# TickTagREV4.net
KiCad netlist of a schematic drawn in EAGLE
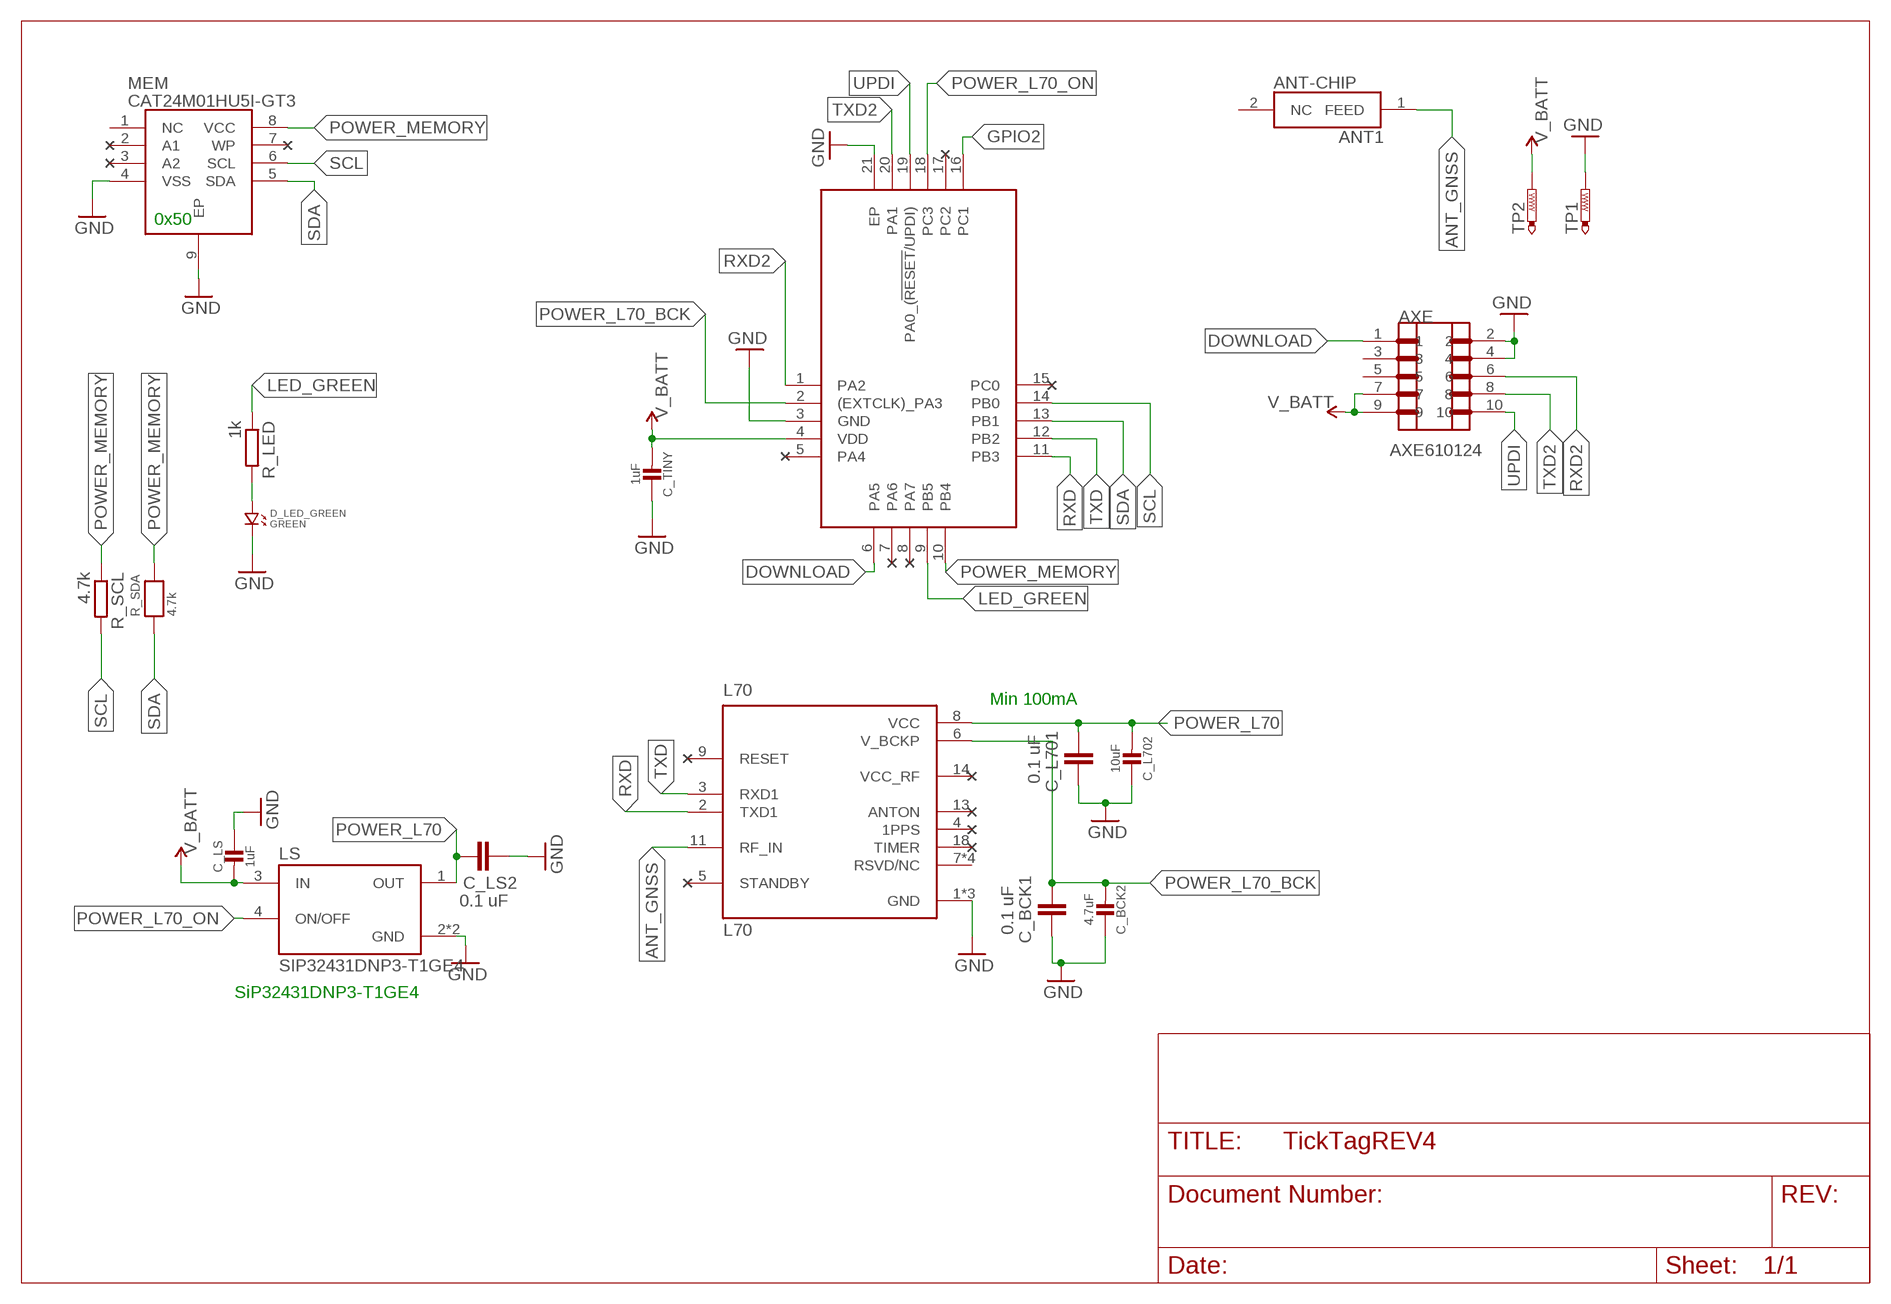
[diagram p0: schematic, sheet 1]

(export (version "E")
  (design (tool "Eeschema 10.0.6"))
  (components
    (comp (ref "ANT-CHIP")
      (value "ANT1")
      (footprint "eagle-import:SAMACSYS_PARTS_1575AT43A0040E")
      (fields
        (field (name "MANUFACTURER_PART_NUMBER") "1575AT43A0040E")
        (field (name "MOUSER_PART_NUMBER") "609-1575AT43A0040E")
      )
      (libsource (lib "eagle-import") (part "SAMACSYS_PARTS_1575AT43A0040E"))
    )
    (comp (ref "ATTINY")
      (value "ATTINY1616-MFR")
      (footprint "eagle-import:QFN40P300X300X90-21N")
      (fields
        (field (name "MANUFACTURER_PART_NUMBER") "ATTINY1606-MFR")
        (field (name "MOUSER_PART_NUMBER") "556-ATTINY1606-MFR")
      )
      (libsource (lib "eagle-import") (part "ATTINY1616-MFR"))
    )
    (comp (ref "AXE")
      (value "AXE610124")
      (footprint "eagle-import:AXE610124")
      (libsource (lib "eagle-import") (part "AXE610124"))
    )
    (comp (ref "C_BCK1")
      (value "0.1 uF")
      (footprint "eagle-import:C0201")
      (libsource (lib "eagle-import") (part "C-EUC0201"))
    )
    (comp (ref "C_BCK2")
      (value "4.7uF")
      (footprint "eagle-import:MICROBUILDER__0402MP")
      (libsource (lib "eagle-import") (part "MICROBUILDER_CAP_CERAMIC_0402MP"))
    )
    (comp (ref "C_L701")
      (value "0.1 uF")
      (footprint "eagle-import:C0201")
      (libsource (lib "eagle-import") (part "C-EUC0201"))
    )
    (comp (ref "C_L702")
      (value "10uF")
      (footprint "eagle-import:MICROBUILDER__0402MP")
      (libsource (lib "eagle-import") (part "MICROBUILDER_CAP_CERAMIC_0402MP"))
    )
    (comp (ref "C_LS")
      (value "1uF")
      (footprint "eagle-import:MICROBUILDER__0402MP")
      (libsource (lib "eagle-import") (part "MICROBUILDER_CAP_CERAMIC_0402MP"))
    )
    (comp (ref "C_LS2")
      (value "0.1 uF")
      (footprint "eagle-import:C0201")
      (libsource (lib "eagle-import") (part "C-EUC0201"))
    )
    (comp (ref "C_TINY")
      (value "1uF")
      (footprint "eagle-import:MICROBUILDER__0402MP")
      (libsource (lib "eagle-import") (part "MICROBUILDER_CAP_CERAMIC_0402MP"))
    )
    (comp (ref "D_LED_GREEN")
      (value "GREEN")
      (footprint "eagle-import:CMONR_STANDARDPARTS_0402.LED")
      (libsource (lib "eagle-import") (part "CMONR_STANDARDPARTS_LED.0402"))
    )
    (comp (ref "L70")
      (value "L70")
      (footprint "eagle-import:XCVR_L70")
      (fields (field (name "MF") "Quectel"))
      (libsource (lib "eagle-import") (part "L70"))
    )
    (comp (ref "LS")
      (value "SIP32431DNP3-T1GE4")
      (footprint "eagle-import:SON50P120X160X60-5N")
      (fields (field (name "MF") "Vishay Siliconix"))
      (libsource (lib "eagle-import") (part "SIP32431DNP3-T1GE4"))
    )
    (comp (ref "MEM")
      (value "CAT24M01HU5I-GT3")
      (footprint "eagle-import:SON50P300X200X55-9N")
      (fields
        (field (name "MOUSER_PART_NUMBER") "863-CAT24M01HU5I-GT3")
        (field (name "RS_PART_NUMBER") "7814831P")
      )
      (libsource (lib "eagle-import") (part "CAT24M01HU5I-GT3"))
    )
    (comp (ref "R_LED")
      (value "1k")
      (footprint "eagle-import:R0201")
      (libsource (lib "eagle-import") (part "R-EU_R0201"))
    )
    (comp (ref "R_SCL")
      (value "4.7k")
      (footprint "eagle-import:R0201")
      (libsource (lib "eagle-import") (part "R-EU_R0201"))
    )
    (comp (ref "R_SDA")
      (value "4.7k")
      (footprint "eagle-import:MICROBUILDER__0402MP")
      (libsource (lib "eagle-import") (part "MICROBUILDER_RESISTOR_0402MP"))
    )
    (comp (ref "TP1")
      (value "PTR1TP13SQ")
      (footprint "eagle-import:TP13SQ")
      (libsource (lib "eagle-import") (part "PTR1TP13SQ"))
    )
    (comp (ref "TP2")
      (value "PTR1TP13SQ")
      (footprint "eagle-import:TP13SQ")
      (libsource (lib "eagle-import") (part "PTR1TP13SQ"))
    )
  )
  (nets
    (net (code "1") (name "ANT_GNSS") (class "Default")
      (node (ref "ANT-CHIP") (pin "1") (pinfunction "FEED_1") (pintype "input"))
      (node (ref "L70") (pin "11") (pinfunction "RF_IN_11") (pintype "input"))
    )
    (net (code "2") (name "DOWNLOAD") (class "Default")
      (node (ref "ATTINY") (pin "6") (pinfunction "PA5_6") (pintype "bidirectional"))
      (node (ref "AXE") (pin "1") (pinfunction "1_1") (pintype "passive"))
    )
    (net (code "3") (name "GND") (class "Default")
      (node (ref "ATTINY") (pin "21") (pinfunction "EP_21") (pintype "bidirectional"))
      (node (ref "ATTINY") (pin "3") (pinfunction "GND_3") (pintype "bidirectional"))
      (node (ref "AXE") (pin "2") (pinfunction "2_2") (pintype "passive"))
      (node (ref "AXE") (pin "4") (pinfunction "4_4") (pintype "passive"))
      (node (ref "C_BCK1") (pin "2") (pinfunction "2_2") (pintype "passive"))
      (node (ref "C_BCK2") (pin "1") (pinfunction "1_1") (pintype "passive"))
      (node (ref "C_L701") (pin "2") (pinfunction "2_2") (pintype "passive"))
      (node (ref "C_L702") (pin "1") (pinfunction "1_1") (pintype "passive"))
      (node (ref "C_LS") (pin "1") (pinfunction "1_1") (pintype "passive"))
      (node (ref "C_LS2") (pin "2") (pinfunction "2_2") (pintype "passive"))
      (node (ref "C_TINY") (pin "1") (pinfunction "1_1") (pintype "passive"))
      (node (ref "D_LED_GREEN") (pin "P$2") (pinfunction "2_P$2") (pintype "bidirectional"))
      (node (ref "L70") (pin "1") (pinfunction "GND_1") (pintype "power_in"))
      (node (ref "L70") (pin "10") (pinfunction "GND_10") (pintype "power_in"))
      (node (ref "L70") (pin "12") (pinfunction "GND_12") (pintype "power_in"))
      (node (ref "LS") (pin "2") (pinfunction "GND_2") (pintype "power_in"))
      (node (ref "LS") (pin "5") (pinfunction "GND_5") (pintype "power_in"))
      (node (ref "MEM") (pin "4") (pinfunction "VSS_4") (pintype "power_in"))
      (node (ref "MEM") (pin "9") (pinfunction "EP_9") (pintype "bidirectional"))
      (node (ref "TP1") (pin "TP") (pinfunction "TP_TP") (pintype "input"))
    )
    (net (code "4") (name "GPIO2") (class "Default")
      (node (ref "ATTINY") (pin "16") (pinfunction "PC1_16") (pintype "bidirectional"))
    )
    (net (code "5") (name "LED_GREEN") (class "Default")
      (node (ref "ATTINY") (pin "9") (pinfunction "PB5_9") (pintype "bidirectional"))
      (node (ref "R_LED") (pin "1") (pinfunction "1_1") (pintype "passive"))
    )
    (net (code "6") (name "Net-(D_LED_GREEN-1)") (class "Default")
      (node (ref "D_LED_GREEN") (pin "P$1") (pinfunction "1_P$1") (pintype "bidirectional"))
      (node (ref "R_LED") (pin "2") (pinfunction "2_2") (pintype "passive"))
    )
    (net (code "7") (name "POWER_L70") (class "Default")
      (node (ref "C_L701") (pin "1") (pinfunction "1_1") (pintype "passive"))
      (node (ref "C_L702") (pin "2") (pinfunction "2_2") (pintype "passive"))
      (node (ref "C_LS2") (pin "1") (pinfunction "1_1") (pintype "passive"))
      (node (ref "L70") (pin "8") (pinfunction "VCC_8") (pintype "power_in"))
      (node (ref "LS") (pin "1") (pinfunction "OUT_1") (pintype "output"))
    )
    (net (code "8") (name "POWER_L70_BCK") (class "Default")
      (node (ref "ATTINY") (pin "2") (pinfunction "(EXTCLK)_PA3_2") (pintype "bidirectional"))
      (node (ref "C_BCK1") (pin "1") (pinfunction "1_1") (pintype "passive"))
      (node (ref "C_BCK2") (pin "2") (pinfunction "2_2") (pintype "passive"))
      (node (ref "L70") (pin "6") (pinfunction "V_BCKP_6") (pintype "power_in"))
    )
    (net (code "9") (name "POWER_L70_ON") (class "Default")
      (node (ref "ATTINY") (pin "18") (pinfunction "PC3_18") (pintype "bidirectional"))
      (node (ref "LS") (pin "4") (pinfunction "ON/OFF_4") (pintype "input"))
    )
    (net (code "10") (name "POWER_MEMORY") (class "Default")
      (node (ref "ATTINY") (pin "10") (pinfunction "PB4_10") (pintype "bidirectional"))
      (node (ref "MEM") (pin "8") (pinfunction "VCC_8") (pintype "power_in"))
      (node (ref "R_SCL") (pin "1") (pinfunction "1_1") (pintype "passive"))
      (node (ref "R_SDA") (pin "2") (pinfunction "2_2") (pintype "passive"))
    )
    (net (code "11") (name "RXD") (class "Default")
      (node (ref "ATTINY") (pin "11") (pinfunction "PB3_11") (pintype "bidirectional"))
      (node (ref "L70") (pin "2") (pinfunction "TXD1_2") (pintype "output"))
    )
    (net (code "12") (name "RXD2") (class "Default")
      (node (ref "ATTINY") (pin "1") (pinfunction "PA2_1") (pintype "bidirectional"))
      (node (ref "AXE") (pin "6") (pinfunction "6_6") (pintype "passive"))
    )
    (net (code "13") (name "SCL") (class "Default")
      (node (ref "ATTINY") (pin "14") (pinfunction "PB0_14") (pintype "bidirectional"))
      (node (ref "MEM") (pin "6") (pinfunction "SCL_6") (pintype "bidirectional"))
      (node (ref "R_SCL") (pin "2") (pinfunction "2_2") (pintype "passive"))
    )
    (net (code "14") (name "SDA") (class "Default")
      (node (ref "ATTINY") (pin "13") (pinfunction "PB1_13") (pintype "bidirectional"))
      (node (ref "MEM") (pin "5") (pinfunction "SDA_5") (pintype "bidirectional"))
      (node (ref "R_SDA") (pin "1") (pinfunction "1_1") (pintype "passive"))
    )
    (net (code "15") (name "TXD") (class "Default")
      (node (ref "ATTINY") (pin "12") (pinfunction "PB2_12") (pintype "bidirectional"))
      (node (ref "L70") (pin "3") (pinfunction "RXD1_3") (pintype "input"))
    )
    (net (code "16") (name "TXD2") (class "Default")
      (node (ref "ATTINY") (pin "20") (pinfunction "PA1_20") (pintype "bidirectional"))
      (node (ref "AXE") (pin "8") (pinfunction "8_8") (pintype "passive"))
    )
    (net (code "17") (name "UPDI") (class "Default")
      (node (ref "ATTINY") (pin "19") (pinfunction "PA0_(~{RESET}/UPDI)_19") (pintype "bidirectional"))
      (node (ref "AXE") (pin "10") (pinfunction "10_10") (pintype "passive"))
    )
    (net (code "18") (name "V_BATT") (class "Default")
      (node (ref "ATTINY") (pin "4") (pinfunction "VDD_4") (pintype "bidirectional"))
      (node (ref "AXE") (pin "7") (pinfunction "7_7") (pintype "passive"))
      (node (ref "AXE") (pin "9") (pinfunction "9_9") (pintype "passive"))
      (node (ref "C_LS") (pin "2") (pinfunction "2_2") (pintype "passive"))
      (node (ref "C_TINY") (pin "2") (pinfunction "2_2") (pintype "passive"))
      (node (ref "LS") (pin "3") (pinfunction "IN_3") (pintype "input"))
      (node (ref "TP2") (pin "TP") (pinfunction "TP_TP") (pintype "input"))
    )
    (net (code "19") (name "unconnected-(ANT-CHIP-NC-Pad2)") (class "Default")
      (node (ref "ANT-CHIP") (pin "2") (pinfunction "NC_2") (pintype "no_connect"))
    )
    (net (code "20") (name "unconnected-(ATTINY-PA4-Pad5)") (class "Default")
      (node (ref "ATTINY") (pin "5") (pinfunction "PA4_5") (pintype "bidirectional"))
    )
    (net (code "21") (name "unconnected-(ATTINY-PA6-Pad7)") (class "Default")
      (node (ref "ATTINY") (pin "7") (pinfunction "PA6_7") (pintype "bidirectional"))
    )
    (net (code "22") (name "unconnected-(ATTINY-PA7-Pad8)") (class "Default")
      (node (ref "ATTINY") (pin "8") (pinfunction "PA7_8") (pintype "bidirectional"))
    )
    (net (code "23") (name "unconnected-(ATTINY-PC0-Pad15)") (class "Default")
      (node (ref "ATTINY") (pin "15") (pinfunction "PC0_15") (pintype "bidirectional"))
    )
    (net (code "24") (name "unconnected-(ATTINY-PC2-Pad17)") (class "Default")
      (node (ref "ATTINY") (pin "17") (pinfunction "PC2_17") (pintype "bidirectional"))
    )
    (net (code "25") (name "unconnected-(AXE-Pad3)") (class "Default")
      (node (ref "AXE") (pin "3") (pinfunction "3_3") (pintype "passive"))
    )
    (net (code "26") (name "unconnected-(AXE-Pad5)") (class "Default")
      (node (ref "AXE") (pin "5") (pinfunction "5_5") (pintype "passive"))
    )
    (net (code "27") (name "unconnected-(L70-1PPS-Pad4)") (class "Default")
      (node (ref "L70") (pin "4") (pinfunction "1PPS_4") (pintype "output"))
    )
    (net (code "28") (name "unconnected-(L70-ANTON-Pad13)") (class "Default")
      (node (ref "L70") (pin "13") (pinfunction "ANTON_13") (pintype "output"))
    )
    (net (code "29") (name "unconnected-(L70-RESET-Pad9)") (class "Default")
      (node (ref "L70") (pin "9") (pinfunction "RESET_9") (pintype "input"))
    )
    (net (code "30") (name "unconnected-(L70-RSVD{slash}NC-Pad7)") (class "Default")
      (node (ref "L70") (pin "7") (pinfunction "RSVD/NC_7") (pintype "no_connect"))
    )
    (net (code "31") (name "unconnected-(L70-RSVD{slash}NC-Pad15)") (class "Default")
      (node (ref "L70") (pin "15") (pinfunction "RSVD/NC_15") (pintype "no_connect"))
    )
    (net (code "32") (name "unconnected-(L70-RSVD{slash}NC-Pad16)") (class "Default")
      (node (ref "L70") (pin "16") (pinfunction "RSVD/NC_16") (pintype "no_connect"))
    )
    (net (code "33") (name "unconnected-(L70-RSVD{slash}NC-Pad17)") (class "Default")
      (node (ref "L70") (pin "17") (pinfunction "RSVD/NC_17") (pintype "no_connect"))
    )
    (net (code "34") (name "unconnected-(L70-STANDBY-Pad5)") (class "Default")
      (node (ref "L70") (pin "5") (pinfunction "STANDBY_5") (pintype "input"))
    )
    (net (code "35") (name "unconnected-(L70-TIMER-Pad18)") (class "Default")
      (node (ref "L70") (pin "18") (pinfunction "TIMER_18") (pintype "output"))
    )
    (net (code "36") (name "unconnected-(L70-VCC_RF-Pad14)") (class "Default")
      (node (ref "L70") (pin "14") (pinfunction "VCC_RF_14") (pintype "output"))
    )
    (net (code "37") (name "unconnected-(MEM-A1-Pad2)") (class "Default")
      (node (ref "MEM") (pin "2") (pinfunction "A1_2") (pintype "bidirectional"))
    )
    (net (code "38") (name "unconnected-(MEM-A2-Pad3)") (class "Default")
      (node (ref "MEM") (pin "3") (pinfunction "A2_3") (pintype "bidirectional"))
    )
    (net (code "39") (name "unconnected-(MEM-NC-Pad1)") (class "Default")
      (node (ref "MEM") (pin "1") (pinfunction "NC_1") (pintype "no_connect"))
    )
    (net (code "40") (name "unconnected-(MEM-WP-Pad7)") (class "Default")
      (node (ref "MEM") (pin "7") (pinfunction "WP_7") (pintype "bidirectional"))
    )
  )
)
